# Power_CAN.net
KiCad netlist of a schematic drawn in Altium Designer
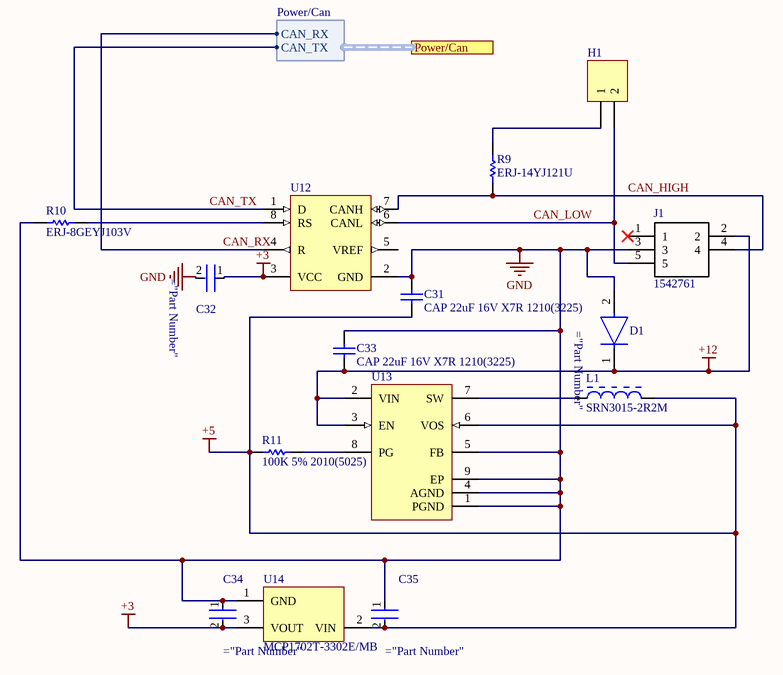
[diagram p0: Power_CAN.SchDoc]

(export (version "E")
  (design (tool "Eeschema 10.0.6"))
  (components
    (comp (ref "C31")
      (value "CAP 22uF 16V X7R 1210(3225)")
      (footprint "CAPC1210(3225)280_L")
      (description "CAP 22uF 16V ±10% 1210 (3225 Metric) Thickness 2.8mm SMD")
      (fields (field (name "TOLERANCE") "Â±10%"))
      (libsource (lib "Altium Content Vault") (part "CAP"))
    )
    (comp (ref "C32")
      (value "C0603C104K5RACTU")
      (footprint "Kemet_C0805_IPC_A")
      (libsource (lib "UNK_Kemet_C0603C104K5RACTU_eec") (part "C0603C104K5RACTU"))
    )
    (comp (ref "C33")
      (value "CAP 22uF 16V X7R 1210(3225)")
      (footprint "CAPC1210(3225)280_L")
      (description "CAP 22uF 16V ±10% 1210 (3225 Metric) Thickness 2.8mm SMD")
      (fields (field (name "TOLERANCE") "Â±10%"))
      (libsource (lib "Altium Content Vault") (part "CAP"))
    )
    (comp (ref "C34")
      (value "C0805C105K4RACTU")
      (footprint "Kemet_C0805_IPC_A")
      (libsource (lib "Cap_Kemet_C0805C105K4RACTU_eec") (part "C0805C105K4RACTU"))
    )
    (comp (ref "C35")
      (value "C0805C105K4RACTU")
      (footprint "Kemet_C0805_IPC_A")
      (libsource (lib "Cap_Kemet_C0805C105K4RACTU_eec") (part "C0805C105K4RACTU"))
    )
    (comp (ref "D1")
      (value "S1J-13-F")
      (footprint "Diodes_SMA_0")
      (libsource (lib "Diode_Diodes_S1J-13-F_eec") (part "S1J-13-F"))
    )
    (comp (ref "H1")
      (value "Header 0")
      (footprint "HDR1X2")
      (description "Header, 2-Pin")
      (fields (field (name "PUBLISHER") "Altium Limited"))
      (libsource (lib "Miscellaneous Connectors") (part "Header 2"))
    )
    (comp (ref "J1")
      (value "1542761")
      (footprint "SamacSys:1542761")
      (description "Connector")
      (fields (field (name "MOUSER PART NUMBER") "651-1542761") (field (name "RS PART NUMBER") "8025583"))
      (libsource (lib "*") (part "1542761"))
    )
    (comp (ref "L1")
      (value "SRN3015-2R2M")
      (footprint "BOUR-SRN3015-2_V")
      (fields (field (name "MANUFACTURER") "Bourns"))
      (libsource (lib "Altium Content Vault") (part "BOUR-IND-2A"))
    )
    (comp (ref "R9")
      (value "ERJ-14YJ121U")
      (footprint "RESC3225X70X50ML20T20")
      (fields (field (name "MANUFACTURER") "Panasonic"))
      (libsource (lib "Altium Content Vault") (part "RES"))
    )
    (comp (ref "R10")
      (value "ERJ-8GEYJ103V")
      (footprint "RESC3216X70X50NL05T20")
      (fields (field (name "MANUFACTURER") "Panasonic"))
      (libsource (lib "Altium Content Vault") (part "RES"))
    )
    (comp (ref "R11")
      (value "100K 5% 2010(5025)")
      (footprint "RESC2010(5025)_L")
      (description "100K 0.75W 5% 2010 (5025 Metric)  SMD")
      (fields (field (name "POWER") "0.75 W") (field (name "TOLERANCE") "5 %"))
      (libsource (lib "Altium Content Vault") (part "RES"))
    )
    (comp (ref "U12")
      (value "SN65HVD230D")
      (footprint "D0008A_M")
      (description "CAN Bus Transceiver, 3.3 V, -40 to 85 degC, 8-Pin SOIC (D), Green (RoHS & no Sb/Br), Tube")
      (fields (field (name "GENERIC PART NUMBER") "SN65HVD230"))
      (libsource (lib "Altium Content Vault") (part "TI-SN65HVD230D-SOIC_D-8"))
    )
    (comp (ref "U13")
      (value "TPS62173DSGR")
      (footprint "DSG8-1600X900TP")
      (fields (field (name "MANUFACTURER") "Texas Instruments"))
      (libsource (lib "Components - 19.05.19 - 16.01") (part "TI-TPS62173DSG8-1600X900TP"))
    )
    (comp (ref "U14")
      (value "MCP1702T-3302E/MB")
      (footprint "SOT-89-MB3_N")
      (description "250 mA Low Quiescent Current LDO Regulator, 3-Pin SOT-89, Extended Temperature, Tape and Reel")
      (libsource (lib "Altium Content Vault") (part "PM-LINEREG-MCP1702-IL3A"))
    )
  )
  (nets
    (net (code "2") (name "+3") (class "Default")
      (node (ref "C32") (pin "1") (pinfunction "1_1") (pintype "passive"))
      (node (ref "C34") (pin "2") (pinfunction "2_2") (pintype "passive"))
      (node (ref "U12") (pin "3") (pinfunction "VCC_3") (pintype "power_in"))
      (node (ref "U14") (pin "3") (pinfunction "VOUT_3") (pintype "power_in"))
    )
    (net (code "3") (name "+5") (class "Default")
      (node (ref "C31") (pin "1") (pinfunction "1_1") (pintype "passive"))
      (node (ref "C35") (pin "2") (pinfunction "2_2") (pintype "passive"))
      (node (ref "L1") (pin "2") (pinfunction "2_2") (pintype "passive"))
      (node (ref "R11") (pin "1") (pinfunction "1_1") (pintype "passive"))
      (node (ref "U13") (pin "6") (pinfunction "VOS_6") (pintype "input"))
      (node (ref "U14") (pin "2") (pinfunction "VIN_2") (pintype "power_in"))
    )
    (net (code "4") (name "+12") (class "Default")
      (node (ref "C33") (pin "1") (pinfunction "1_1") (pintype "passive"))
      (node (ref "D1") (pin "1") (pinfunction "C_1") (pintype "passive"))
      (node (ref "J1") (pin "2") (pinfunction "2_2") (pintype "passive"))
      (node (ref "U13") (pin "2") (pinfunction "VIN_2") (pintype "power_in"))
      (node (ref "U13") (pin "3") (pinfunction "EN_3") (pintype "input"))
    )
    (net (code "5") (name "/CAN_HIGH") (class "Default")
      (node (ref "J1") (pin "4") (pinfunction "4_4") (pintype "passive"))
      (node (ref "R9") (pin "1") (pinfunction "1_1") (pintype "passive"))
      (node (ref "U12") (pin "7") (pinfunction "CANH_7") (pintype "bidirectional"))
    )
    (net (code "6") (name "/CAN_LOW") (class "Default")
      (node (ref "H1") (pin "2") (pinfunction "2_2") (pintype "passive"))
      (node (ref "J1") (pin "5") (pinfunction "5_5") (pintype "passive"))
      (node (ref "U12") (pin "6") (pinfunction "CANL_6") (pintype "bidirectional"))
    )
    (net (code "7") (name "/CAN_RX") (class "Default")
      (node (ref "U12") (pin "4") (pinfunction "R_4") (pintype "output"))
    )
    (net (code "8") (name "/CAN_TX") (class "Default")
      (node (ref "U12") (pin "1") (pinfunction "D_1") (pintype "input"))
    )
    (net (code "10") (name "GND") (class "Default")
      (node (ref "C31") (pin "2") (pinfunction "2_2") (pintype "passive"))
      (node (ref "C32") (pin "2") (pinfunction "2_2") (pintype "passive"))
      (node (ref "C33") (pin "2") (pinfunction "2_2") (pintype "passive"))
      (node (ref "C34") (pin "1") (pinfunction "1_1") (pintype "passive"))
      (node (ref "C35") (pin "1") (pinfunction "1_1") (pintype "passive"))
      (node (ref "D1") (pin "2") (pinfunction "A_2") (pintype "passive"))
      (node (ref "J1") (pin "3") (pinfunction "3_3") (pintype "passive"))
      (node (ref "R10") (pin "2") (pinfunction "2_2") (pintype "passive"))
      (node (ref "U12") (pin "2") (pinfunction "GND_2") (pintype "power_in"))
      (node (ref "U13") (pin "1") (pinfunction "PGND_1") (pintype "power_in"))
      (node (ref "U13") (pin "4") (pinfunction "AGND_4") (pintype "power_in"))
      (node (ref "U13") (pin "5") (pinfunction "FB_5") (pintype "passive"))
      (node (ref "U13") (pin "9") (pinfunction "EP_9") (pintype "power_in"))
      (node (ref "U14") (pin "1") (pinfunction "GND_1") (pintype "power_in"))
    )
    (net (code "11") (name "Net-(H1-Pad1)") (class "Default")
      (node (ref "H1") (pin "1") (pinfunction "1_1") (pintype "passive"))
      (node (ref "R9") (pin "2") (pinfunction "2_2") (pintype "passive"))
    )
    (net (code "12") (name "Net-(U12-RS)") (class "Default")
      (node (ref "R10") (pin "1") (pinfunction "1_1") (pintype "passive"))
      (node (ref "U12") (pin "8") (pinfunction "RS_8") (pintype "input"))
    )
    (net (code "13") (name "Net-(U13-PG)") (class "Default")
      (node (ref "R11") (pin "2") (pinfunction "2_2") (pintype "passive"))
      (node (ref "U13") (pin "8") (pinfunction "PG_8") (pintype "tri_state"))
    )
    (net (code "14") (name "Net-(U13-SW)") (class "Default")
      (node (ref "L1") (pin "1") (pinfunction "1_1") (pintype "passive"))
      (node (ref "U13") (pin "7") (pinfunction "SW_7") (pintype "power_in"))
    )
    (net (code "15") (name "unconnected-(J1-Pad1)") (class "Default")
      (node (ref "J1") (pin "1") (pinfunction "1_1") (pintype "passive+no_connect"))
    )
    (net (code "16") (name "unconnected-(U12-VREF-Pad5)") (class "Default")
      (node (ref "U12") (pin "5") (pinfunction "VREF_5") (pintype "output"))
    )
  )
)
